# DigitalInput.net
KiCad netlist of a schematic drawn in Altium Designer
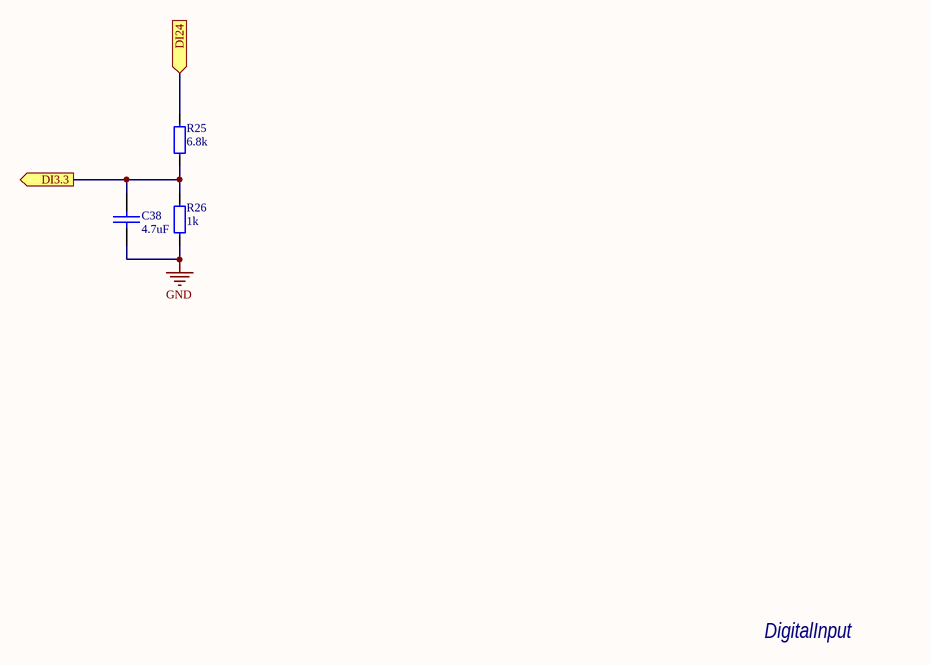
[diagram p0: DigitalInput.SchDoc]

(export (version "E")
  (design (tool "Eeschema 10.0.6"))
  (components
    (comp (ref "C38")
      (value "4.7uF")
      (footprint "0603 Capicator")
      (description "4.7uF X5R 25V 10% 0603")
      (fields
        (field (name "MANUFACTURER") "Murata Manufacturing")
        (field (name "PART NUMBER") "GRM188R61E475KE11D")
      )
      (libsource (lib "БУНЭ") (part "Cap 4.7uF (0603)"))
    )
    (comp (ref "R25")
      (value "6.8k")
      (footprint "0603 Resistor")
      (description "0.1W 0603 6.8k, 1%")
      (fields (field (name "PART NUMBER") "RC0603FR-076K8L") (field (name "MANUFACTURER") "Taiwan"))
      (libsource (lib "БУНЭ") (part "Res 6.8k (0603)"))
    )
    (comp (ref "R26")
      (value "1k")
      (footprint "0603 Resistor")
      (description "0.1W 0603 1k, 1%")
      (fields (field (name "PART NUMBER") "RC0603FR-071KL") (field (name "MANUFACTURER") "Taiwan"))
      (libsource (lib "БУНЭ") (part "Res 1k (0603)"))
    )
  )
  (nets
    (net (code "1") (name "/DI3.3") (class "Default")
      (node (ref "C38") (pin "2") (pinfunction "2_2") (pintype "passive"))
      (node (ref "R25") (pin "1") (pinfunction "1_1") (pintype "passive"))
      (node (ref "R26") (pin "2") (pinfunction "2_2") (pintype "passive"))
    )
    (net (code "2") (name "/DI24") (class "Default")
      (node (ref "R25") (pin "2") (pinfunction "2_2") (pintype "passive"))
    )
    (net (code "3") (name "GND") (class "Default")
      (node (ref "C38") (pin "1") (pinfunction "1_1") (pintype "passive"))
      (node (ref "R26") (pin "1") (pinfunction "1_1") (pintype "passive"))
    )
  )
)
